# SensWear_PPG.net
KiCad netlist of a schematic drawn in Altium Designer
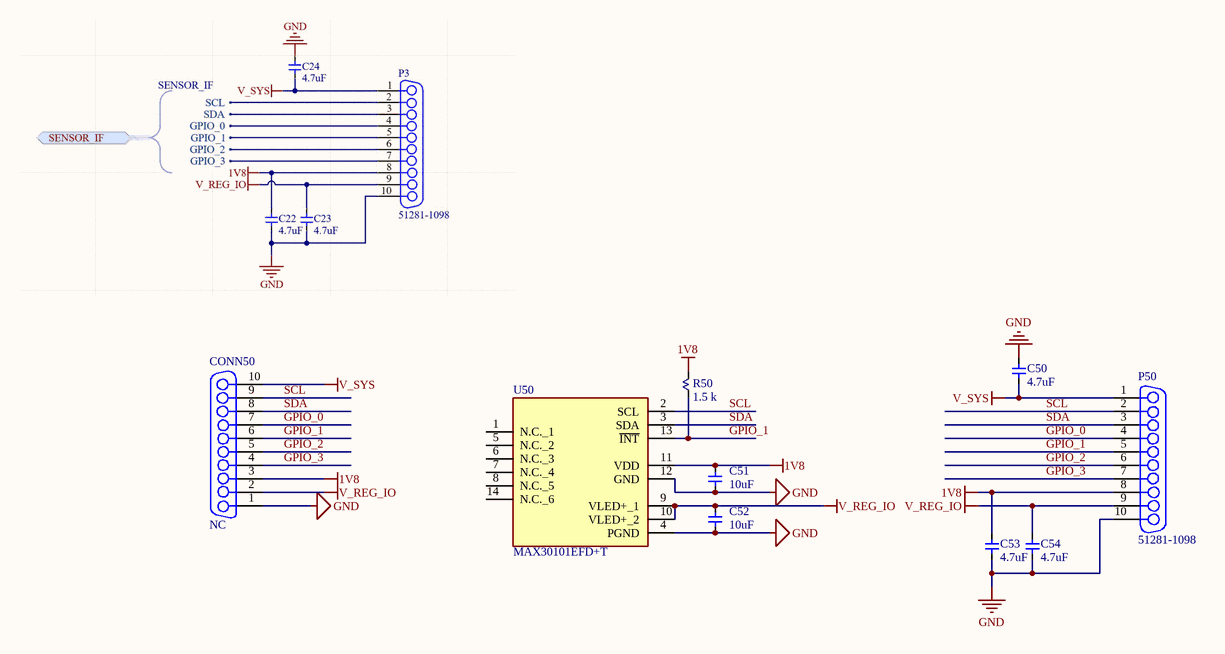
[diagram p0: SensWear_PPG.SchDoc]

(export (version "E")
  (design (tool "Eeschema 10.0.6"))
  (components
    (comp (ref "C50")
      (value "4.7uF")
      (footprint "CAPC1005X05N")
      (description "Multilayer Ceramic Capacitor, 4.7 uF, 10 V, ± 20%, X5R, 0402 [1005 Metric]")
      (fields
        (field (name "MANUFACTURER") "Murata")
        (field (name "MANUFACTURER PART NUMBER") "GRM155R61A475MEAAD")
      )
      (libsource (lib "OpenRingComponents") (part "GRM155R61A475MEAAD"))
    )
    (comp (ref "C51")
      (value "10uF")
      (footprint "CAPC1005X05N")
      (description "Multilayer Ceramic Capacitor, 10 uF, 10 V, ± 20%, X5R, 0402 [1005 Metric]")
      (fields
        (field (name "MANUFACTURER") "Samsung")
        (field (name "MANUFACTURER PART NUMBER") "CL05A106MP5NUNC")
      )
      (libsource (lib "OpenRingComponents") (part "CL05A106MP5NUNC"))
    )
    (comp (ref "C52")
      (value "10uF")
      (footprint "CAPC1005X05N")
      (description "Multilayer Ceramic Capacitor, 10 uF, 10 V, ± 20%, X5R, 0402 [1005 Metric]")
      (fields
        (field (name "MANUFACTURER") "Samsung")
        (field (name "MANUFACTURER PART NUMBER") "CL05A106MP5NUNC")
      )
      (libsource (lib "OpenRingComponents") (part "CL05A106MP5NUNC"))
    )
    (comp (ref "C53")
      (value "4.7uF")
      (footprint "CAPC1005X05N")
      (description "Multilayer Ceramic Capacitor, 4.7 uF, 10 V, ± 20%, X5R, 0402 [1005 Metric]")
      (fields
        (field (name "MANUFACTURER") "Murata")
        (field (name "MANUFACTURER PART NUMBER") "GRM155R61A475MEAAD")
      )
      (libsource (lib "OpenRingComponents") (part "GRM155R61A475MEAAD"))
    )
    (comp (ref "C54")
      (value "4.7uF")
      (footprint "CAPC1005X05N")
      (description "Multilayer Ceramic Capacitor, 4.7 uF, 10 V, ± 20%, X5R, 0402 [1005 Metric]")
      (fields
        (field (name "MANUFACTURER") "Murata")
        (field (name "MANUFACTURER PART NUMBER") "GRM155R61A475MEAAD")
      )
      (libsource (lib "OpenRingComponents") (part "GRM155R61A475MEAAD"))
    )
    (comp (ref "CONN50")
      (value "NC")
      (footprint "51281-1098-PCB")
      (libsource (lib "Connectors") (part "51281-1098-PCB"))
    )
    (comp (ref "P50")
      (value "51281-1098")
      (footprint "51281-1098")
      (description "FFC/FPC Connector, Surface Mount, Right-Angle, Non-ZIF, Dual Contact Style")
      (fields (field (name "MANUFACTURER") "Molex"))
      (libsource (lib "Connectors") (part "51281-1098"))
    )
    (comp (ref "R50")
      (value "1.5 k")
      (footprint "RESC1005X04N")
      (description "RES SMD 1.5K OHM 1% 1/10W 0402")
      (fields
        (field (name "MANUFACTURER") "Panasonic Electronic Components")
        (field (name "MANUFACTURER PART NUMBER") "ERJ-2RKF1501X")
      )
      (libsource (lib "OpenRingComponents") (part "ERJ-2RKF1501X"))
    )
    (comp (ref "U50")
      (value "MAX30101EFD+T")
      (footprint "14-LEAD-OESIP")
      (description "High-Sensitivity Pulse Oximeter and Heart-Rate Sensor for Fitness & Healthcare")
      (fields (field (name "MANUFACTURER") "Maxim"))
      (libsource (lib "Modules") (part "MAX30101EFD+T"))
    )
  )
  (nets
    (net (code "1") (name "/GPIO_0") (class "Default")
      (node (ref "CONN50") (pin "7") (pinfunction "7_7") (pintype "passive"))
      (node (ref "P50") (pin "4") (pinfunction "4_4") (pintype "passive"))
    )
    (net (code "2") (name "/GPIO_1") (class "Default")
      (node (ref "CONN50") (pin "6") (pinfunction "6_6") (pintype "passive"))
      (node (ref "P50") (pin "5") (pinfunction "5_5") (pintype "passive"))
      (node (ref "R50") (pin "1") (pinfunction "1_1") (pintype "passive"))
      (node (ref "U50") (pin "13") (pinfunction "~{INT}_13") (pintype "passive"))
    )
    (net (code "3") (name "/GPIO_2") (class "Default")
      (node (ref "CONN50") (pin "5") (pinfunction "5_5") (pintype "passive"))
      (node (ref "P50") (pin "6") (pinfunction "6_6") (pintype "passive"))
    )
    (net (code "4") (name "/GPIO_3") (class "Default")
      (node (ref "CONN50") (pin "4") (pinfunction "4_4") (pintype "passive"))
      (node (ref "P50") (pin "7") (pinfunction "7_7") (pintype "passive"))
    )
    (net (code "5") (name "/SCL") (class "Default")
      (node (ref "CONN50") (pin "9") (pinfunction "9_9") (pintype "passive"))
      (node (ref "P50") (pin "2") (pinfunction "2_2") (pintype "passive"))
      (node (ref "U50") (pin "2") (pinfunction "SCL_2") (pintype "passive"))
    )
    (net (code "6") (name "/SDA") (class "Default")
      (node (ref "CONN50") (pin "8") (pinfunction "8_8") (pintype "passive"))
      (node (ref "P50") (pin "3") (pinfunction "3_3") (pintype "passive"))
      (node (ref "U50") (pin "3") (pinfunction "SDA_3") (pintype "passive"))
    )
    (net (code "7") (name "1V8") (class "Default")
      (node (ref "C51") (pin "2") (pinfunction "2_2") (pintype "passive"))
      (node (ref "C53") (pin "2") (pinfunction "2_2") (pintype "passive"))
      (node (ref "CONN50") (pin "3") (pinfunction "3_3") (pintype "passive"))
      (node (ref "P50") (pin "8") (pinfunction "8_8") (pintype "passive"))
      (node (ref "R50") (pin "2") (pinfunction "2_2") (pintype "passive"))
      (node (ref "U50") (pin "11") (pinfunction "VDD_11") (pintype "passive"))
    )
    (net (code "8") (name "GND") (class "Default")
      (node (ref "C50") (pin "2") (pinfunction "2_2") (pintype "passive"))
      (node (ref "C51") (pin "1") (pinfunction "1_1") (pintype "passive"))
      (node (ref "C52") (pin "2") (pinfunction "2_2") (pintype "passive"))
      (node (ref "C53") (pin "1") (pinfunction "1_1") (pintype "passive"))
      (node (ref "C54") (pin "1") (pinfunction "1_1") (pintype "passive"))
      (node (ref "CONN50") (pin "1") (pinfunction "1_1") (pintype "passive"))
      (node (ref "P50") (pin "10") (pinfunction "10_10") (pintype "passive"))
      (node (ref "U50") (pin "12") (pinfunction "GND_12") (pintype "passive"))
      (node (ref "U50") (pin "4") (pinfunction "PGND_4") (pintype "passive"))
    )
    (net (code "9") (name "V_REG_IO") (class "Default")
      (node (ref "C52") (pin "1") (pinfunction "1_1") (pintype "passive"))
      (node (ref "C54") (pin "2") (pinfunction "2_2") (pintype "passive"))
      (node (ref "CONN50") (pin "2") (pinfunction "2_2") (pintype "passive"))
      (node (ref "P50") (pin "9") (pinfunction "9_9") (pintype "passive"))
      (node (ref "U50") (pin "10") (pinfunction "VLED+_2_10") (pintype "passive"))
      (node (ref "U50") (pin "9") (pinfunction "VLED+_1_9") (pintype "passive"))
    )
    (net (code "10") (name "V_SYS") (class "Default")
      (node (ref "C50") (pin "1") (pinfunction "1_1") (pintype "passive"))
      (node (ref "CONN50") (pin "10") (pinfunction "10_10") (pintype "passive"))
      (node (ref "P50") (pin "1") (pinfunction "1_1") (pintype "passive"))
    )
    (net (code "11") (name "unconnected-(U50-N.C._1-Pad1)") (class "Default")
      (node (ref "U50") (pin "1") (pinfunction "N.C._1_1") (pintype "passive"))
    )
    (net (code "12") (name "unconnected-(U50-N.C._2-Pad5)") (class "Default")
      (node (ref "U50") (pin "5") (pinfunction "N.C._2_5") (pintype "passive"))
    )
    (net (code "13") (name "unconnected-(U50-N.C._3-Pad6)") (class "Default")
      (node (ref "U50") (pin "6") (pinfunction "N.C._3_6") (pintype "passive"))
    )
    (net (code "14") (name "unconnected-(U50-N.C._4-Pad7)") (class "Default")
      (node (ref "U50") (pin "7") (pinfunction "N.C._4_7") (pintype "passive"))
    )
    (net (code "15") (name "unconnected-(U50-N.C._5-Pad8)") (class "Default")
      (node (ref "U50") (pin "8") (pinfunction "N.C._5_8") (pintype "passive"))
    )
    (net (code "16") (name "unconnected-(U50-N.C._6-Pad14)") (class "Default")
      (node (ref "U50") (pin "14") (pinfunction "N.C._6_14") (pintype "passive"))
    )
  )
)
